# 2022_AESK_UAV_Islemci.net
KiCad netlist of a schematic drawn in Altium Designer
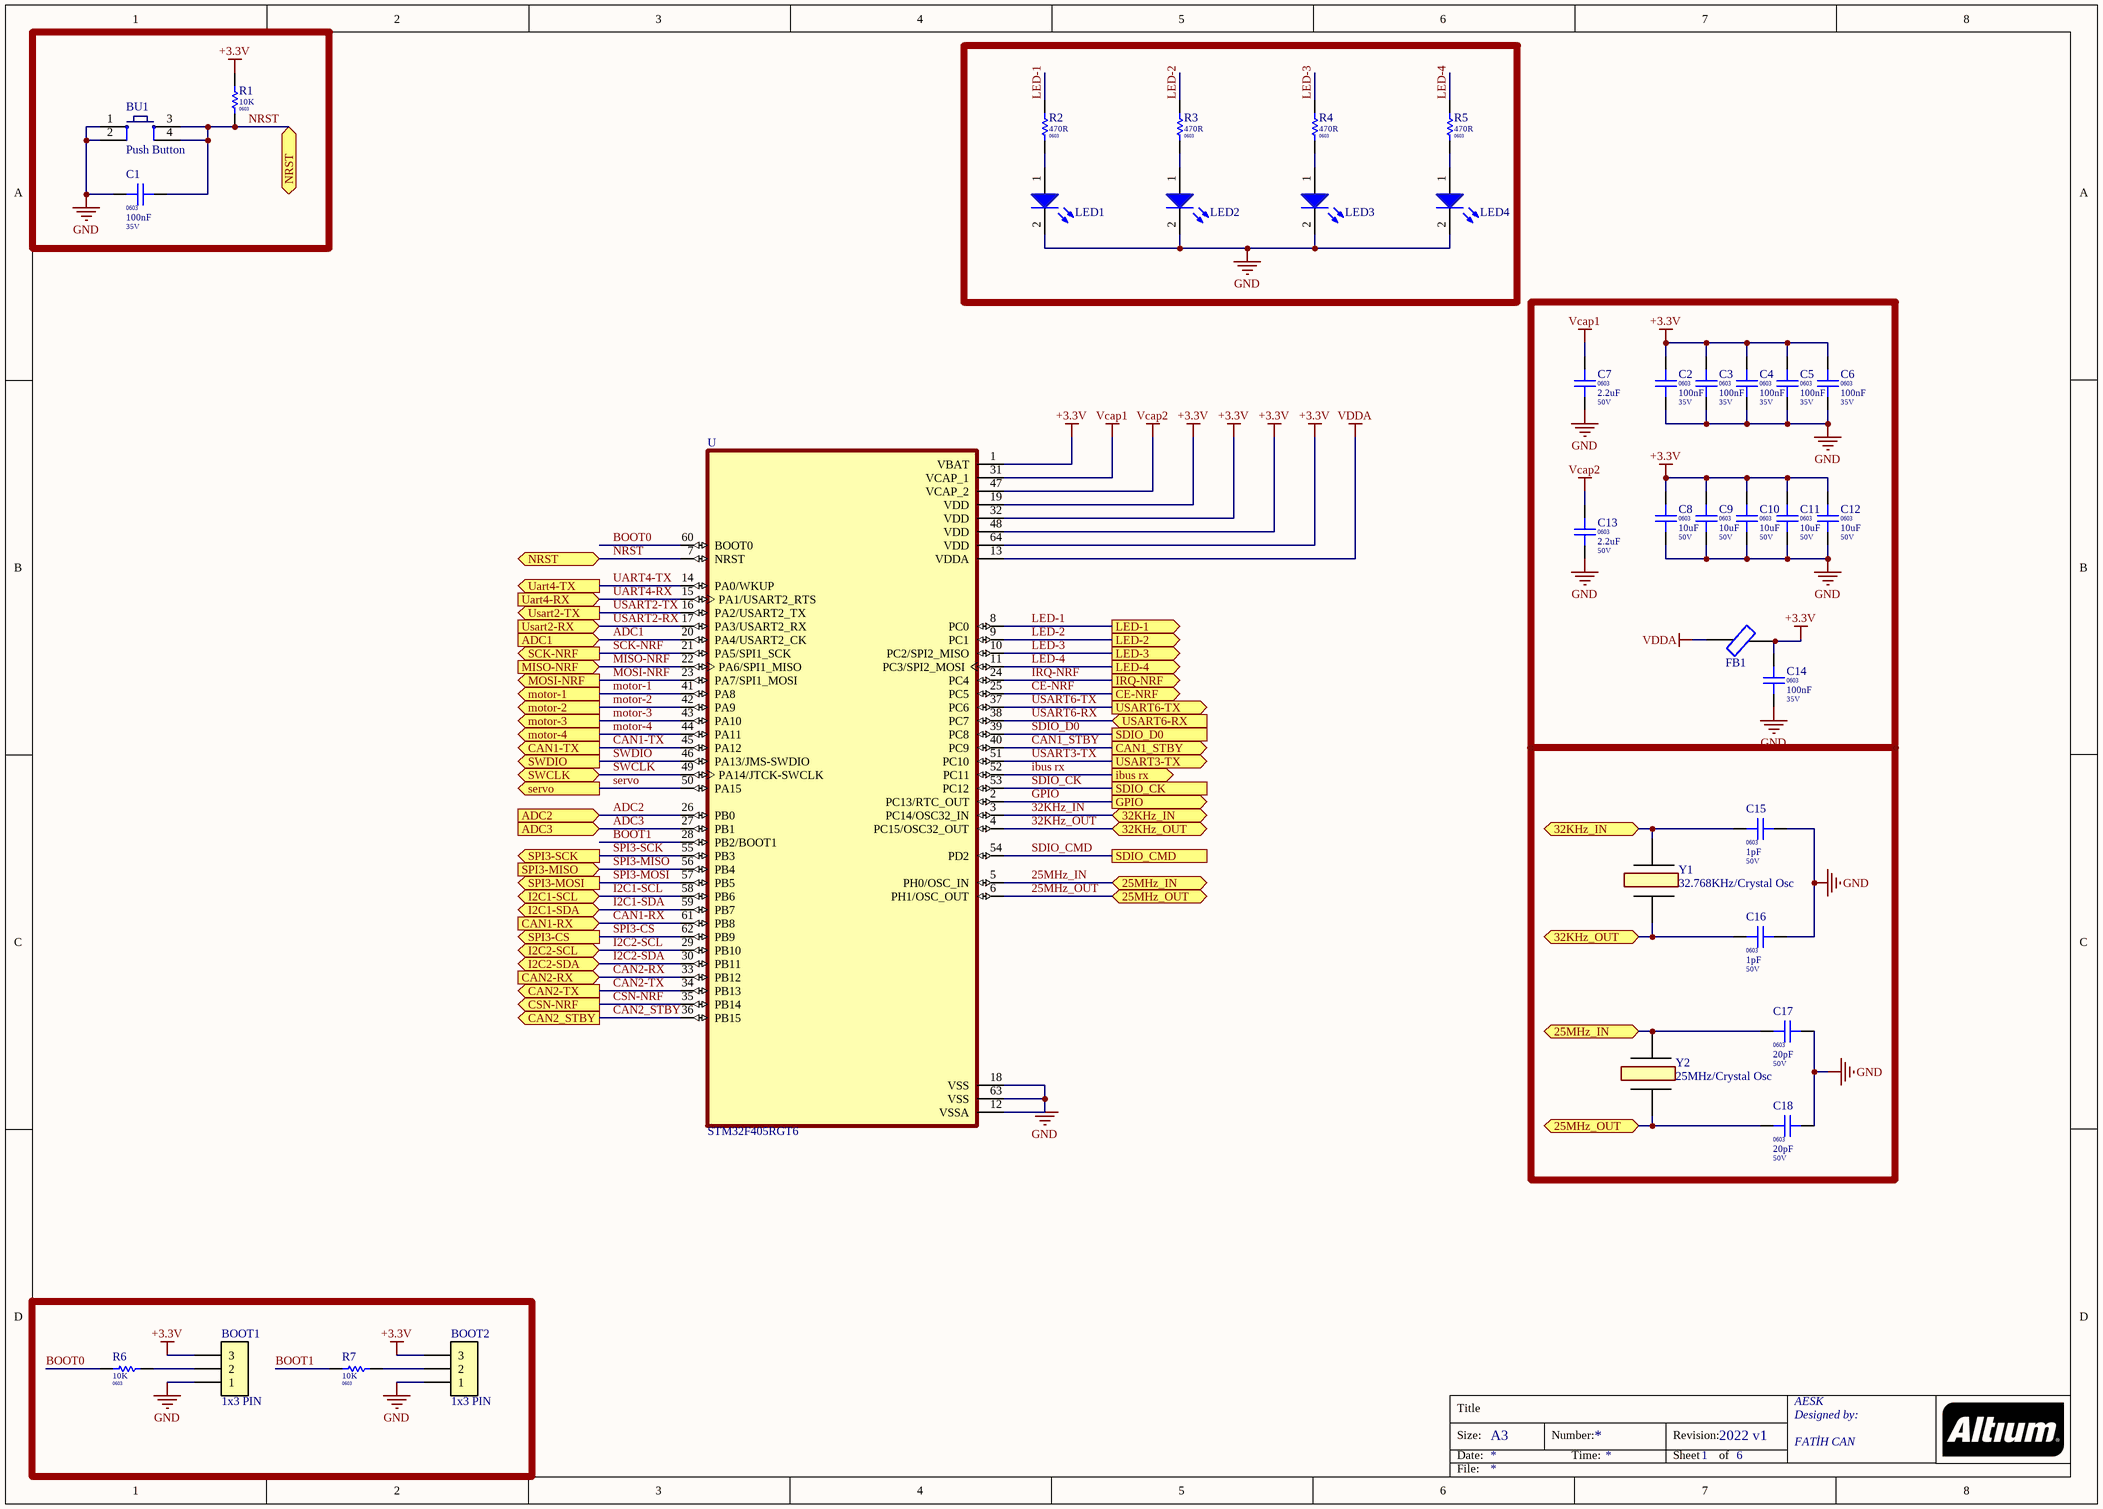
[diagram p0: 2022_AESK_UAV_Islemci.SchDoc]

(export (version "E")
  (design (tool "Eeschema 10.0.6"))
  (components
    (comp (ref "BOOT1")
      (value "1x3 PIN")
      (footprint "HDR_2.54_1X3")
      (description "Header 2.54 1x3")
      (fields (field (name "PART NUMBER") "Connector0009"))
      (libsource (lib "Aesk Database Library") (part "1x3 PIN"))
    )
    (comp (ref "BOOT2")
      (value "1x3 PIN")
      (footprint "HDR_2.54_1X3")
      (description "Header 2.54 1x3")
      (fields (field (name "PART NUMBER") "Connector0009"))
      (libsource (lib "Aesk Database Library") (part "1x3 PIN"))
    )
    (comp (ref "BU1")
      (value "Push Button")
      (footprint "button son")
      (description "Smd Push Button")
      (libsource (lib "UAV_UcusKontrolKartı_Sematik_Kutuphane") (part "Push Button"))
    )
    (comp (ref "C1")
      (value "100nF")
      (footprint "CAPC 0603")
      (description "Capacitor Ceramic 100nF 35V 0603")
      (fields
        (field (name "TOLERANCE") "%10")
        (field (name "PACKAGE / CASE") "0603")
        (field (name "VOLTAGE") "35V")
        (field (name "PART NUMBER") "CAPC0328")
      )
      (libsource (lib "Aesk Database Library") (part "NPCapacitor"))
    )
    (comp (ref "C2")
      (value "100nF")
      (footprint "CAPC 0603")
      (description "Capacitor Ceramic 100nF 35V 0603")
      (fields
        (field (name "TOLERANCE") "%10")
        (field (name "PACKAGE / CASE") "0603")
        (field (name "VOLTAGE") "35V")
        (field (name "PART NUMBER") "CAPC0328")
      )
      (libsource (lib "Aesk Database Library") (part "NPCapacitor"))
    )
    (comp (ref "C3")
      (value "100nF")
      (footprint "CAPC 0603")
      (description "Capacitor Ceramic 100nF 35V 0603")
      (fields
        (field (name "TOLERANCE") "%10")
        (field (name "PACKAGE / CASE") "0603")
        (field (name "VOLTAGE") "35V")
        (field (name "PART NUMBER") "CAPC0328")
      )
      (libsource (lib "Aesk Database Library") (part "NPCapacitor"))
    )
    (comp (ref "C4")
      (value "100nF")
      (footprint "CAPC 0603")
      (description "Capacitor Ceramic 100nF 35V 0603")
      (fields
        (field (name "TOLERANCE") "%10")
        (field (name "PACKAGE / CASE") "0603")
        (field (name "VOLTAGE") "35V")
        (field (name "PART NUMBER") "CAPC0328")
      )
      (libsource (lib "Aesk Database Library") (part "NPCapacitor"))
    )
    (comp (ref "C5")
      (value "100nF")
      (footprint "CAPC 0603")
      (description "Capacitor Ceramic 100nF 35V 0603")
      (fields
        (field (name "TOLERANCE") "%10")
        (field (name "PACKAGE / CASE") "0603")
        (field (name "VOLTAGE") "35V")
        (field (name "PART NUMBER") "CAPC0328")
      )
      (libsource (lib "Aesk Database Library") (part "NPCapacitor"))
    )
    (comp (ref "C6")
      (value "100nF")
      (footprint "CAPC 0603")
      (description "Capacitor Ceramic 100nF 35V 0603")
      (fields
        (field (name "TOLERANCE") "%10")
        (field (name "PACKAGE / CASE") "0603")
        (field (name "VOLTAGE") "35V")
        (field (name "PART NUMBER") "CAPC0328")
      )
      (libsource (lib "Aesk Database Library") (part "NPCapacitor"))
    )
    (comp (ref "C7")
      (value "2.2uF")
      (footprint "CAPC 0603")
      (description "Capacitor Ceramic 2.2uF 50V 0603")
      (fields
        (field (name "TOLERANCE") "%10")
        (field (name "PACKAGE / CASE") "0603")
        (field (name "VOLTAGE") "50V")
        (field (name "PART NUMBER") "CAPC0295")
      )
      (libsource (lib "AESK Database Library") (part "NPCapacitor"))
    )
    (comp (ref "C8")
      (value "10uF")
      (footprint "CAPC 0603")
      (description "Capacitor Ceramic 10uF 50V 0603")
      (fields
        (field (name "TOLERANCE") "%10")
        (field (name "PACKAGE / CASE") "0603")
        (field (name "VOLTAGE") "50V")
        (field (name "PART NUMBER") "CAPC0301")
      )
      (libsource (lib "Aesk Database Library") (part "NPCapacitor"))
    )
    (comp (ref "C9")
      (value "10uF")
      (footprint "CAPC 0603")
      (description "Capacitor Ceramic 10uF 50V 0603")
      (fields
        (field (name "TOLERANCE") "%10")
        (field (name "PACKAGE / CASE") "0603")
        (field (name "VOLTAGE") "50V")
        (field (name "PART NUMBER") "CAPC0301")
      )
      (libsource (lib "Aesk Database Library") (part "NPCapacitor"))
    )
    (comp (ref "C10")
      (value "10uF")
      (footprint "CAPC 0603")
      (description "Capacitor Ceramic 10uF 50V 0603")
      (fields
        (field (name "TOLERANCE") "%10")
        (field (name "PACKAGE / CASE") "0603")
        (field (name "VOLTAGE") "50V")
        (field (name "PART NUMBER") "CAPC0301")
      )
      (libsource (lib "Aesk Database Library") (part "NPCapacitor"))
    )
    (comp (ref "C11")
      (value "10uF")
      (footprint "CAPC 0603")
      (description "Capacitor Ceramic 10uF 50V 0603")
      (fields
        (field (name "TOLERANCE") "%10")
        (field (name "PACKAGE / CASE") "0603")
        (field (name "VOLTAGE") "50V")
        (field (name "PART NUMBER") "CAPC0301")
      )
      (libsource (lib "Aesk Database Library") (part "NPCapacitor"))
    )
    (comp (ref "C12")
      (value "10uF")
      (footprint "CAPC 0603")
      (description "Capacitor Ceramic 10uF 50V 0603")
      (fields
        (field (name "TOLERANCE") "%10")
        (field (name "PACKAGE / CASE") "0603")
        (field (name "VOLTAGE") "50V")
        (field (name "PART NUMBER") "CAPC0301")
      )
      (libsource (lib "Aesk Database Library") (part "NPCapacitor"))
    )
    (comp (ref "C13")
      (value "2.2uF")
      (footprint "CAPC 0603")
      (description "Capacitor Ceramic 2.2uF 50V 0603")
      (fields
        (field (name "TOLERANCE") "%10")
        (field (name "PACKAGE / CASE") "0603")
        (field (name "VOLTAGE") "50V")
        (field (name "PART NUMBER") "CAPC0295")
      )
      (libsource (lib "AESK Database Library") (part "NPCapacitor"))
    )
    (comp (ref "C14")
      (value "100nF")
      (footprint "CAPC 0603")
      (description "Capacitor Ceramic 100nF 35V 0603")
      (fields
        (field (name "TOLERANCE") "%10")
        (field (name "PACKAGE / CASE") "0603")
        (field (name "VOLTAGE") "35V")
        (field (name "PART NUMBER") "CAPC0328")
      )
      (libsource (lib "Aesk Database Library") (part "NPCapacitor"))
    )
    (comp (ref "C15")
      (value "1pF")
      (footprint "CAPC 0603")
      (description "Capacitor Ceramic 1pF 50V 0603")
      (fields
        (field (name "TOLERANCE") "%10")
        (field (name "PACKAGE / CASE") "0603")
        (field (name "VOLTAGE") "50V")
        (field (name "PART NUMBER") "CAPC0233")
      )
      (libsource (lib "AESK Database Library") (part "NPCapacitor"))
    )
    (comp (ref "C16")
      (value "1pF")
      (footprint "CAPC 0603")
      (description "Capacitor Ceramic 1pF 50V 0603")
      (fields
        (field (name "TOLERANCE") "%10")
        (field (name "PACKAGE / CASE") "0603")
        (field (name "VOLTAGE") "50V")
        (field (name "PART NUMBER") "CAPC0233")
      )
      (libsource (lib "AESK Database Library") (part "NPCapacitor"))
    )
    (comp (ref "C17")
      (value "20pF")
      (footprint "CAPC 0603")
      (description "Capacitor Ceramic 20pF 50V 0603")
      (fields
        (field (name "TOLERANCE") "%10")
        (field (name "PACKAGE / CASE") "0603")
        (field (name "VOLTAGE") "50V")
        (field (name "PART NUMBER") "CAPC0246")
      )
      (libsource (lib "AESK Database Library") (part "NPCapacitor"))
    )
    (comp (ref "C18")
      (value "20pF")
      (footprint "CAPC 0603")
      (description "Capacitor Ceramic 20pF 50V 0603")
      (fields
        (field (name "TOLERANCE") "%10")
        (field (name "PACKAGE / CASE") "0603")
        (field (name "VOLTAGE") "50V")
        (field (name "PART NUMBER") "CAPC0246")
      )
      (libsource (lib "AESK Database Library") (part "NPCapacitor"))
    )
    (comp (ref "FB1")
      (value "Ferrite Bead")
      (footprint "FCM1608KF-601T03")
      (libsource (lib "2022_AESK_UAV") (part "FCM1608KF-601T03"))
    )
    (comp (ref "LED1")
      (value "~")
      (footprint "LED BLUE 0603")
      (description "LED")
      (libsource (lib "Diodes_GESK") (part "LED BLUE"))
    )
    (comp (ref "LED2")
      (value "~")
      (footprint "LED BLUE 0603")
      (description "LED")
      (libsource (lib "Diodes_GESK") (part "LED BLUE"))
    )
    (comp (ref "LED3")
      (value "~")
      (footprint "LED BLUE 0603")
      (description "LED")
      (libsource (lib "Diodes_GESK") (part "LED BLUE"))
    )
    (comp (ref "LED4")
      (value "~")
      (footprint "LED BLUE 0603")
      (description "LED")
      (libsource (lib "Diodes_GESK") (part "LED BLUE"))
    )
    (comp (ref "R1")
      (value "10K")
      (footprint "RESC 0603")
      (description "10K 0603")
      (fields
        (field (name "TOLERANCE") "%5")
        (field (name "POWER") "1/10W")
        (field (name "PACKAGE / CASE") "0603")
      )
      (libsource (lib "Aesk Database Library") (part "Resistor"))
    )
    (comp (ref "R2")
      (value "470R")
      (footprint "RESC 0603")
      (description "470R 0603")
      (fields
        (field (name "TOLERANCE") "%5")
        (field (name "POWER") "1/10W")
        (field (name "PACKAGE / CASE") "0603")
      )
      (libsource (lib "AESK Database Library") (part "Resistor"))
    )
    (comp (ref "R3")
      (value "470R")
      (footprint "RESC 0603")
      (description "470R 0603")
      (fields
        (field (name "TOLERANCE") "%5")
        (field (name "POWER") "1/10W")
        (field (name "PACKAGE / CASE") "0603")
      )
      (libsource (lib "AESK Database Library") (part "Resistor"))
    )
    (comp (ref "R4")
      (value "470R")
      (footprint "RESC 0603")
      (description "470R 0603")
      (fields
        (field (name "TOLERANCE") "%5")
        (field (name "POWER") "1/10W")
        (field (name "PACKAGE / CASE") "0603")
      )
      (libsource (lib "AESK Database Library") (part "Resistor"))
    )
    (comp (ref "R5")
      (value "470R")
      (footprint "RESC 0603")
      (description "470R 0603")
      (fields
        (field (name "TOLERANCE") "%5")
        (field (name "POWER") "1/10W")
        (field (name "PACKAGE / CASE") "0603")
      )
      (libsource (lib "AESK Database Library") (part "Resistor"))
    )
    (comp (ref "R6")
      (value "10K")
      (footprint "RESC 0603")
      (description "10K 0603")
      (fields
        (field (name "TOLERANCE") "%5")
        (field (name "POWER") "1/10W")
        (field (name "PACKAGE / CASE") "0603")
      )
      (libsource (lib "AESK Database Library") (part "Resistor"))
    )
    (comp (ref "R7")
      (value "10K")
      (footprint "RESC 0603")
      (description "10K 0603")
      (fields
        (field (name "TOLERANCE") "%5")
        (field (name "POWER") "1/10W")
        (field (name "PACKAGE / CASE") "0603")
      )
      (libsource (lib "AESK Database Library") (part "Resistor"))
    )
    (comp (ref "U")
      (value "STM32F405RGT6")
      (footprint "QFP50P1200X1200X160-64N")
      (description "ARMÂ® CortexÂ®-M4 STM32F4 Microcontroller IC 32-Bit 168MHz 1MB _1M x 8_ FLASH 64-LQFP _10x10_")
      (fields (field (name "MF") "STMicroelectronics") (field (name "DIGI-KEY_PART_NUMBER") "497-11767-ND"))
      (libsource (lib "2022_AESK_UAV") (part "STM32F405RGT6"))
    )
    (comp (ref "Y1")
      (value "32.768KHz/Crystal Osc")
      (footprint "32KhZ crystal oscillator")
      (description "Crystal or Oscillator")
      (libsource (lib "2022_AESK_UAV") (part "NX3215SA-32.768KHZ-EXS00A-MU00525"))
    )
    (comp (ref "Y2")
      (value "25MHz/Crystal Osc")
      (footprint "25MHz Crystal Oscillator")
      (description "Crystal or Oscillator")
      (libsource (lib "2022_AESK_UAV") (part "ECS-250-18-5PX-F-TR"))
    )
  )
  (nets
    (net (code "1") (name "+3.3V") (class "Default")
      (node (ref "BOOT1") (pin "3") (pinfunction "3_3") (pintype "passive"))
      (node (ref "BOOT2") (pin "3") (pinfunction "3_3") (pintype "passive"))
      (node (ref "C10") (pin "2") (pinfunction "2_2") (pintype "passive"))
      (node (ref "C11") (pin "2") (pinfunction "2_2") (pintype "passive"))
      (node (ref "C12") (pin "2") (pinfunction "2_2") (pintype "passive"))
      (node (ref "C14") (pin "2") (pinfunction "2_2") (pintype "passive"))
      (node (ref "C2") (pin "2") (pinfunction "2_2") (pintype "passive"))
      (node (ref "C3") (pin "2") (pinfunction "2_2") (pintype "passive"))
      (node (ref "C4") (pin "2") (pinfunction "2_2") (pintype "passive"))
      (node (ref "C5") (pin "2") (pinfunction "2_2") (pintype "passive"))
      (node (ref "C6") (pin "2") (pinfunction "2_2") (pintype "passive"))
      (node (ref "C8") (pin "2") (pinfunction "2_2") (pintype "passive"))
      (node (ref "C9") (pin "2") (pinfunction "2_2") (pintype "passive"))
      (node (ref "FB1") (pin "2") (pinfunction "2_2") (pintype "passive"))
      (node (ref "R1") (pin "1") (pinfunction "1_1") (pintype "passive"))
      (node (ref "U") (pin "1") (pinfunction "VBAT_1") (pintype "power_in"))
      (node (ref "U") (pin "19") (pinfunction "VDD_19") (pintype "power_in"))
      (node (ref "U") (pin "32") (pinfunction "VDD_32") (pintype "power_in"))
      (node (ref "U") (pin "48") (pinfunction "VDD_48") (pintype "power_in"))
      (node (ref "U") (pin "64") (pinfunction "VDD_64") (pintype "power_in"))
    )
    (net (code "2") (name "/25MHz_IN") (class "Default")
      (node (ref "C17") (pin "1") (pinfunction "1_1") (pintype "passive"))
      (node (ref "U") (pin "5") (pinfunction "PH0/OSC_IN_5") (pintype "bidirectional"))
      (node (ref "Y2") (pin "2") (pinfunction "2_2") (pintype "passive"))
    )
    (net (code "3") (name "/25MHz_OUT") (class "Default")
      (node (ref "C18") (pin "1") (pinfunction "1_1") (pintype "passive"))
      (node (ref "U") (pin "6") (pinfunction "PH1/OSC_OUT_6") (pintype "bidirectional"))
      (node (ref "Y2") (pin "1") (pinfunction "1_1") (pintype "passive"))
    )
    (net (code "4") (name "/32KHz_IN") (class "Default")
      (node (ref "C15") (pin "1") (pinfunction "1_1") (pintype "passive"))
      (node (ref "U") (pin "3") (pinfunction "PC14/OSC32_IN_3") (pintype "bidirectional"))
      (node (ref "Y1") (pin "2") (pinfunction "2_2") (pintype "passive"))
    )
    (net (code "5") (name "/32KHz_OUT") (class "Default")
      (node (ref "C16") (pin "1") (pinfunction "1_1") (pintype "passive"))
      (node (ref "U") (pin "4") (pinfunction "PC15/OSC32_OUT_4") (pintype "bidirectional"))
      (node (ref "Y1") (pin "1") (pinfunction "1_1") (pintype "passive"))
    )
    (net (code "6") (name "/ADC1") (class "Default")
      (node (ref "U") (pin "20") (pinfunction "PA4/USART2_CK_20") (pintype "bidirectional"))
    )
    (net (code "7") (name "/ADC2") (class "Default")
      (node (ref "U") (pin "26") (pinfunction "PB0_26") (pintype "bidirectional"))
    )
    (net (code "8") (name "/ADC3") (class "Default")
      (node (ref "U") (pin "27") (pinfunction "PB1_27") (pintype "bidirectional"))
    )
    (net (code "9") (name "/BOOT0") (class "Default")
      (node (ref "R6") (pin "1") (pinfunction "1_1") (pintype "passive"))
      (node (ref "U") (pin "60") (pinfunction "BOOT0_60") (pintype "bidirectional"))
    )
    (net (code "10") (name "/BOOT1") (class "Default")
      (node (ref "R7") (pin "1") (pinfunction "1_1") (pintype "passive"))
      (node (ref "U") (pin "28") (pinfunction "PB2/BOOT1_28") (pintype "bidirectional"))
    )
    (net (code "11") (name "/CAN1-RX") (class "Default")
      (node (ref "U") (pin "61") (pinfunction "PB8_61") (pintype "bidirectional"))
    )
    (net (code "12") (name "/CAN1-TX") (class "Default")
      (node (ref "U") (pin "45") (pinfunction "PA12_45") (pintype "bidirectional"))
    )
    (net (code "13") (name "/CAN1_STBY") (class "Default")
      (node (ref "U") (pin "40") (pinfunction "PC9_40") (pintype "bidirectional"))
    )
    (net (code "14") (name "/CAN2-RX") (class "Default")
      (node (ref "U") (pin "33") (pinfunction "PB12_33") (pintype "bidirectional"))
    )
    (net (code "15") (name "/CAN2-TX") (class "Default")
      (node (ref "U") (pin "34") (pinfunction "PB13_34") (pintype "bidirectional"))
    )
    (net (code "16") (name "/CAN2_STBY") (class "Default")
      (node (ref "U") (pin "36") (pinfunction "PB15_36") (pintype "bidirectional"))
    )
    (net (code "17") (name "/CE-NRF") (class "Default")
      (node (ref "U") (pin "25") (pinfunction "PC5_25") (pintype "bidirectional"))
    )
    (net (code "18") (name "/CSN-NRF") (class "Default")
      (node (ref "U") (pin "35") (pinfunction "PB14_35") (pintype "bidirectional"))
    )
    (net (code "19") (name "/GPIO") (class "Default")
      (node (ref "U") (pin "2") (pinfunction "PC13/RTC_OUT_2") (pintype "bidirectional"))
    )
    (net (code "20") (name "/I2C1-SCL") (class "Default")
      (node (ref "U") (pin "58") (pinfunction "PB6_58") (pintype "bidirectional"))
    )
    (net (code "21") (name "/I2C1-SDA") (class "Default")
      (node (ref "U") (pin "59") (pinfunction "PB7_59") (pintype "bidirectional"))
    )
    (net (code "22") (name "/I2C2-SCL") (class "Default")
      (node (ref "U") (pin "29") (pinfunction "PB10_29") (pintype "bidirectional"))
    )
    (net (code "23") (name "/I2C2-SDA") (class "Default")
      (node (ref "U") (pin "30") (pinfunction "PB11_30") (pintype "bidirectional"))
    )
    (net (code "24") (name "/IRQ-NRF") (class "Default")
      (node (ref "U") (pin "24") (pinfunction "PC4_24") (pintype "bidirectional"))
    )
    (net (code "25") (name "/LED-1") (class "Default")
      (node (ref "R2") (pin "2") (pinfunction "2_2") (pintype "passive"))
      (node (ref "U") (pin "8") (pinfunction "PC0_8") (pintype "bidirectional"))
    )
    (net (code "26") (name "/LED-2") (class "Default")
      (node (ref "R3") (pin "2") (pinfunction "2_2") (pintype "passive"))
      (node (ref "U") (pin "9") (pinfunction "PC1_9") (pintype "bidirectional"))
    )
    (net (code "27") (name "/LED-3") (class "Default")
      (node (ref "R4") (pin "2") (pinfunction "2_2") (pintype "passive"))
      (node (ref "U") (pin "10") (pinfunction "PC2/SPI2_MISO_10") (pintype "bidirectional"))
    )
    (net (code "28") (name "/LED-4") (class "Default")
      (node (ref "R5") (pin "2") (pinfunction "2_2") (pintype "passive"))
      (node (ref "U") (pin "11") (pinfunction "PC3/SPI2_MOSI_11") (pintype "bidirectional"))
    )
    (net (code "29") (name "/MISO-NRF") (class "Default")
      (node (ref "U") (pin "22") (pinfunction "PA6/SPI1_MISO_22") (pintype "bidirectional"))
    )
    (net (code "30") (name "/MOSI-NRF") (class "Default")
      (node (ref "U") (pin "23") (pinfunction "PA7/SPI1_MOSI_23") (pintype "bidirectional"))
    )
    (net (code "31") (name "/NRST") (class "Default")
      (node (ref "BU1") (pin "3") (pinfunction "3_3") (pintype "passive"))
      (node (ref "BU1") (pin "4") (pinfunction "4_4") (pintype "passive"))
      (node (ref "C1") (pin "2") (pinfunction "2_2") (pintype "passive"))
      (node (ref "R1") (pin "2") (pinfunction "2_2") (pintype "passive"))
      (node (ref "U") (pin "7") (pinfunction "NRST_7") (pintype "bidirectional"))
    )
    (net (code "32") (name "/SCK-NRF") (class "Default")
      (node (ref "U") (pin "21") (pinfunction "PA5/SPI1_SCK_21") (pintype "bidirectional"))
    )
    (net (code "33") (name "/SDIO_CK") (class "Default")
      (node (ref "U") (pin "53") (pinfunction "PC12_53") (pintype "bidirectional"))
    )
    (net (code "34") (name "/SDIO_CMD") (class "Default")
      (node (ref "U") (pin "54") (pinfunction "PD2_54") (pintype "bidirectional"))
    )
    (net (code "35") (name "/SDIO_D0") (class "Default")
      (node (ref "U") (pin "39") (pinfunction "PC8_39") (pintype "bidirectional"))
    )
    (net (code "36") (name "/SPI3-CS") (class "Default")
      (node (ref "U") (pin "62") (pinfunction "PB9_62") (pintype "bidirectional"))
    )
    (net (code "37") (name "/SPI3-MISO") (class "Default")
      (node (ref "U") (pin "56") (pinfunction "PB4_56") (pintype "bidirectional"))
    )
    (net (code "38") (name "/SPI3-MOSI") (class "Default")
      (node (ref "U") (pin "57") (pinfunction "PB5_57") (pintype "bidirectional"))
    )
    (net (code "39") (name "/SPI3-SCK") (class "Default")
      (node (ref "U") (pin "55") (pinfunction "PB3_55") (pintype "bidirectional"))
    )
    (net (code "40") (name "/SWCLK") (class "Default")
      (node (ref "U") (pin "49") (pinfunction "PA14/JTCK-SWCLK_49") (pintype "bidirectional"))
    )
    (net (code "41") (name "/SWDIO") (class "Default")
      (node (ref "U") (pin "46") (pinfunction "PA13/JMS-SWDIO_46") (pintype "bidirectional"))
    )
    (net (code "42") (name "/UART4-RX") (class "Default")
      (node (ref "U") (pin "15") (pinfunction "PA1/USART2_RTS_15") (pintype "bidirectional"))
    )
    (net (code "43") (name "/UART4-TX") (class "Default")
      (node (ref "U") (pin "14") (pinfunction "PA0/WKUP_14") (pintype "bidirectional"))
    )
    (net (code "44") (name "/USART2-RX") (class "Default")
      (node (ref "U") (pin "17") (pinfunction "PA3/USART2_RX_17") (pintype "bidirectional"))
    )
    (net (code "45") (name "/USART2-TX") (class "Default")
      (node (ref "U") (pin "16") (pinfunction "PA2/USART2_TX_16") (pintype "bidirectional"))
    )
    (net (code "46") (name "/USART3-TX") (class "Default")
      (node (ref "U") (pin "51") (pinfunction "PC10_51") (pintype "bidirectional"))
    )
    (net (code "47") (name "/USART6-RX") (class "Default")
      (node (ref "U") (pin "38") (pinfunction "PC7_38") (pintype "bidirectional"))
    )
    (net (code "48") (name "/USART6-TX") (class "Default")
      (node (ref "U") (pin "37") (pinfunction "PC6_37") (pintype "bidirectional"))
    )
    (net (code "49") (name "/ibus rx") (class "Default")
      (node (ref "U") (pin "52") (pinfunction "PC11_52") (pintype "bidirectional"))
    )
    (net (code "50") (name "/motor-1") (class "Default")
      (node (ref "U") (pin "41") (pinfunction "PA8_41") (pintype "bidirectional"))
    )
    (net (code "51") (name "/motor-2") (class "Default")
      (node (ref "U") (pin "42") (pinfunction "PA9_42") (pintype "bidirectional"))
    )
    (net (code "52") (name "/motor-3") (class "Default")
      (node (ref "U") (pin "43") (pinfunction "PA10_43") (pintype "bidirectional"))
    )
    (net (code "53") (name "/motor-4") (class "Default")
      (node (ref "U") (pin "44") (pinfunction "PA11_44") (pintype "bidirectional"))
    )
    (net (code "54") (name "/servo") (class "Default")
      (node (ref "U") (pin "50") (pinfunction "PA15_50") (pintype "bidirectional"))
    )
    (net (code "55") (name "GND") (class "Default")
      (node (ref "BOOT1") (pin "1") (pinfunction "1_1") (pintype "passive"))
      (node (ref "BOOT2") (pin "1") (pinfunction "1_1") (pintype "passive"))
      (node (ref "BU1") (pin "1") (pinfunction "1_1") (pintype "passive"))
      (node (ref "BU1") (pin "2") (pinfunction "2_2") (pintype "passive"))
      (node (ref "C1") (pin "1") (pinfunction "1_1") (pintype "passive"))
      (node (ref "C10") (pin "1") (pinfunction "1_1") (pintype "passive"))
      (node (ref "C11") (pin "1") (pinfunction "1_1") (pintype "passive"))
      (node (ref "C12") (pin "1") (pinfunction "1_1") (pintype "passive"))
      (node (ref "C13") (pin "1") (pinfunction "1_1") (pintype "passive"))
      (node (ref "C14") (pin "1") (pinfunction "1_1") (pintype "passive"))
      (node (ref "C15") (pin "2") (pinfunction "2_2") (pintype "passive"))
      (node (ref "C16") (pin "2") (pinfunction "2_2") (pintype "passive"))
      (node (ref "C17") (pin "2") (pinfunction "2_2") (pintype "passive"))
      (node (ref "C18") (pin "2") (pinfunction "2_2") (pintype "passive"))
      (node (ref "C2") (pin "1") (pinfunction "1_1") (pintype "passive"))
      (node (ref "C3") (pin "1") (pinfunction "1_1") (pintype "passive"))
      (node (ref "C4") (pin "1") (pinfunction "1_1") (pintype "passive"))
      (node (ref "C5") (pin "1") (pinfunction "1_1") (pintype "passive"))
      (node (ref "C6") (pin "1") (pinfunction "1_1") (pintype "passive"))
      (node (ref "C7") (pin "1") (pinfunction "1_1") (pintype "passive"))
      (node (ref "C8") (pin "1") (pinfunction "1_1") (pintype "passive"))
      (node (ref "C9") (pin "1") (pinfunction "1_1") (pintype "passive"))
      (node (ref "LED1") (pin "2") (pinfunction "C_2") (pintype "passive"))
      (node (ref "LED2") (pin "2") (pinfunction "C_2") (pintype "passive"))
      (node (ref "LED3") (pin "2") (pinfunction "C_2") (pintype "passive"))
      (node (ref "LED4") (pin "2") (pinfunction "C_2") (pintype "passive"))
      (node (ref "U") (pin "12") (pinfunction "VSSA_12") (pintype "power_in"))
      (node (ref "U") (pin "18") (pinfunction "VSS_18") (pintype "power_in"))
      (node (ref "U") (pin "63") (pinfunction "VSS_63") (pintype "power_in"))
    )
    (net (code "56") (name "Net-(BOOT1-Pad2)") (class "Default")
      (node (ref "BOOT1") (pin "2") (pinfunction "2_2") (pintype "passive"))
      (node (ref "R6") (pin "2") (pinfunction "2_2") (pintype "passive"))
    )
    (net (code "57") (name "Net-(BOOT2-Pad2)") (class "Default")
      (node (ref "BOOT2") (pin "2") (pinfunction "2_2") (pintype "passive"))
      (node (ref "R7") (pin "2") (pinfunction "2_2") (pintype "passive"))
    )
    (net (code "58") (name "Net-(LED1-A)") (class "Default")
      (node (ref "LED1") (pin "1") (pinfunction "A_1") (pintype "passive"))
      (node (ref "R2") (pin "1") (pinfunction "1_1") (pintype "passive"))
    )
    (net (code "59") (name "Net-(LED2-A)") (class "Default")
      (node (ref "LED2") (pin "1") (pinfunction "A_1") (pintype "passive"))
      (node (ref "R3") (pin "1") (pinfunction "1_1") (pintype "passive"))
    )
    (net (code "60") (name "Net-(LED3-A)") (class "Default")
      (node (ref "LED3") (pin "1") (pinfunction "A_1") (pintype "passive"))
      (node (ref "R4") (pin "1") (pinfunction "1_1") (pintype "passive"))
    )
    (net (code "61") (name "Net-(LED4-A)") (class "Default")
      (node (ref "LED4") (pin "1") (pinfunction "A_1") (pintype "passive"))
      (node (ref "R5") (pin "1") (pinfunction "1_1") (pintype "passive"))
    )
    (net (code "62") (name "VDDA") (class "Default")
      (node (ref "FB1") (pin "1") (pinfunction "1_1") (pintype "passive"))
      (node (ref "U") (pin "13") (pinfunction "VDDA_13") (pintype "power_in"))
    )
    (net (code "63") (name "Vcap1") (class "Default")
      (node (ref "C7") (pin "2") (pinfunction "2_2") (pintype "passive"))
      (node (ref "U") (pin "31") (pinfunction "VCAP_1_31") (pintype "power_in"))
    )
    (net (code "64") (name "Vcap2") (class "Default")
      (node (ref "C13") (pin "2") (pinfunction "2_2") (pintype "passive"))
      (node (ref "U") (pin "47") (pinfunction "VCAP_2_47") (pintype "power_in"))
    )
  )
)
